# magicke_oko.net
KiCad netlist of a schematic drawn in EAGLE
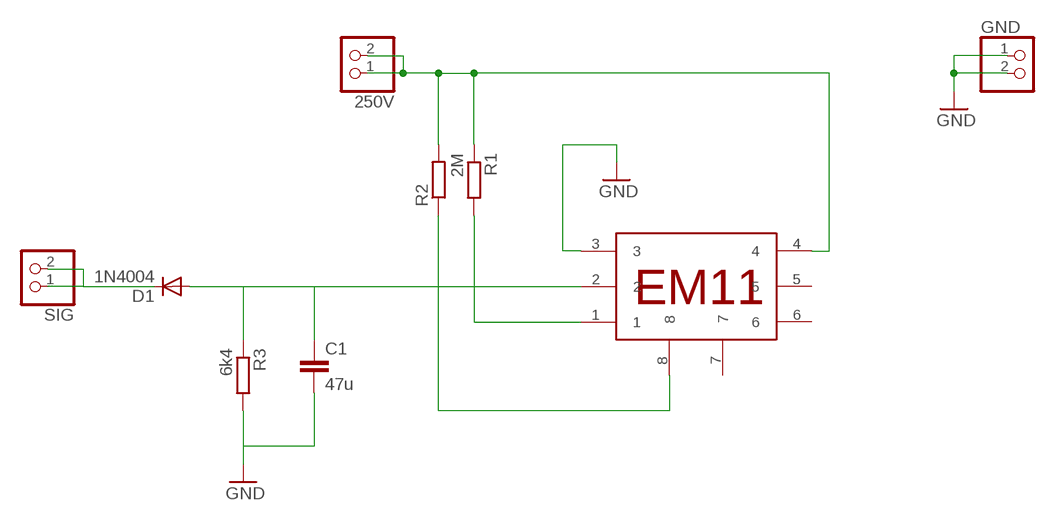
[diagram p0: schematic, sheet 1]

(export (version "E")
  (design (tool "Eeschema 10.0.6"))
  (components
    (comp (ref "250V")
      (value "PINHD-1X2")
      (footprint "eagle-import:1X02")
      (libsource (lib "eagle-import") (part "PINHD-1X2"))
    )
    (comp (ref "C1")
      (value "47u")
      (footprint "eagle-import:C050-075X075")
      (libsource (lib "eagle-import") (part "C-EU050-075X075"))
    )
    (comp (ref "D1")
      (value "1N4004")
      (footprint "eagle-import:DO41-10")
      (libsource (lib "eagle-import") (part "1N4004"))
    )
    (comp (ref "GND")
      (value "PINHD-1X2")
      (footprint "eagle-import:1X02")
      (libsource (lib "eagle-import") (part "PINHD-1X2"))
    )
    (comp (ref "R1")
      (value "2M")
      (footprint "eagle-import:0309_10")
      (libsource (lib "eagle-import") (part "R-EU_0309/10"))
    )
    (comp (ref "R2")
      (value "R-EU_0309/10")
      (footprint "eagle-import:0309_10")
      (libsource (lib "eagle-import") (part "R-EU_0309/10"))
    )
    (comp (ref "R3")
      (value "6k4")
      (footprint "eagle-import:0309_10")
      (libsource (lib "eagle-import") (part "R-EU_0309/10"))
    )
    (comp (ref "SIG")
      (value "PINHD-1X2")
      (footprint "eagle-import:1X02")
      (libsource (lib "eagle-import") (part "PINHD-1X2"))
    )
    (comp (ref "U$1")
      (value "EM11")
      (footprint "eagle-import:EM11_PACKAGE")
      (libsource (lib "eagle-import") (part "EM11"))
    )
  )
  (nets
    (net (code "1") (name "GND") (class "Default")
      (node (ref "C1") (pin "2") (pinfunction "2_2") (pintype "passive"))
      (node (ref "GND") (pin "1") (pinfunction "1_1") (pintype "passive"))
      (node (ref "GND") (pin "2") (pinfunction "2_2") (pintype "passive"))
      (node (ref "R3") (pin "2") (pinfunction "2_2") (pintype "passive"))
      (node (ref "U$1") (pin "3") (pinfunction "3_3") (pintype "bidirectional"))
    )
    (net (code "2") (name "Net-(250V-Pad1)") (class "Default")
      (node (ref "250V") (pin "1") (pinfunction "1_1") (pintype "passive"))
      (node (ref "250V") (pin "2") (pinfunction "2_2") (pintype "passive"))
      (node (ref "R1") (pin "1") (pinfunction "1_1") (pintype "passive"))
      (node (ref "R2") (pin "2") (pinfunction "2_2") (pintype "passive"))
      (node (ref "U$1") (pin "4") (pinfunction "4_4") (pintype "bidirectional"))
    )
    (net (code "3") (name "Net-(C1-Pad1)") (class "Default")
      (node (ref "C1") (pin "1") (pinfunction "1_1") (pintype "passive"))
      (node (ref "D1") (pin "A") (pinfunction "A_A") (pintype "passive"))
      (node (ref "R3") (pin "1") (pinfunction "1_1") (pintype "passive"))
      (node (ref "U$1") (pin "2") (pinfunction "2_2") (pintype "bidirectional"))
    )
    (net (code "4") (name "Net-(D1-PadC)") (class "Default")
      (node (ref "D1") (pin "C") (pinfunction "C_C") (pintype "passive"))
      (node (ref "SIG") (pin "1") (pinfunction "1_1") (pintype "passive"))
      (node (ref "SIG") (pin "2") (pinfunction "2_2") (pintype "passive"))
    )
    (net (code "5") (name "Net-(R1-Pad2)") (class "Default")
      (node (ref "R1") (pin "2") (pinfunction "2_2") (pintype "passive"))
      (node (ref "U$1") (pin "1") (pinfunction "1_1") (pintype "bidirectional"))
    )
    (net (code "6") (name "Net-(R2-Pad1)") (class "Default")
      (node (ref "R2") (pin "1") (pinfunction "1_1") (pintype "passive"))
      (node (ref "U$1") (pin "8") (pinfunction "8_8") (pintype "bidirectional"))
    )
    (net (code "7") (name "unconnected-(U$1-Pad5)") (class "Default")
      (node (ref "U$1") (pin "5") (pinfunction "5_5") (pintype "bidirectional"))
    )
    (net (code "8") (name "unconnected-(U$1-Pad6)") (class "Default")
      (node (ref "U$1") (pin "6") (pinfunction "6_6") (pintype "bidirectional"))
    )
    (net (code "9") (name "unconnected-(U$1-Pad7)") (class "Default")
      (node (ref "U$1") (pin "7") (pinfunction "7_7") (pintype "bidirectional"))
    )
  )
)
